# xl4432.net
KiCad netlist of a schematic drawn in EAGLE
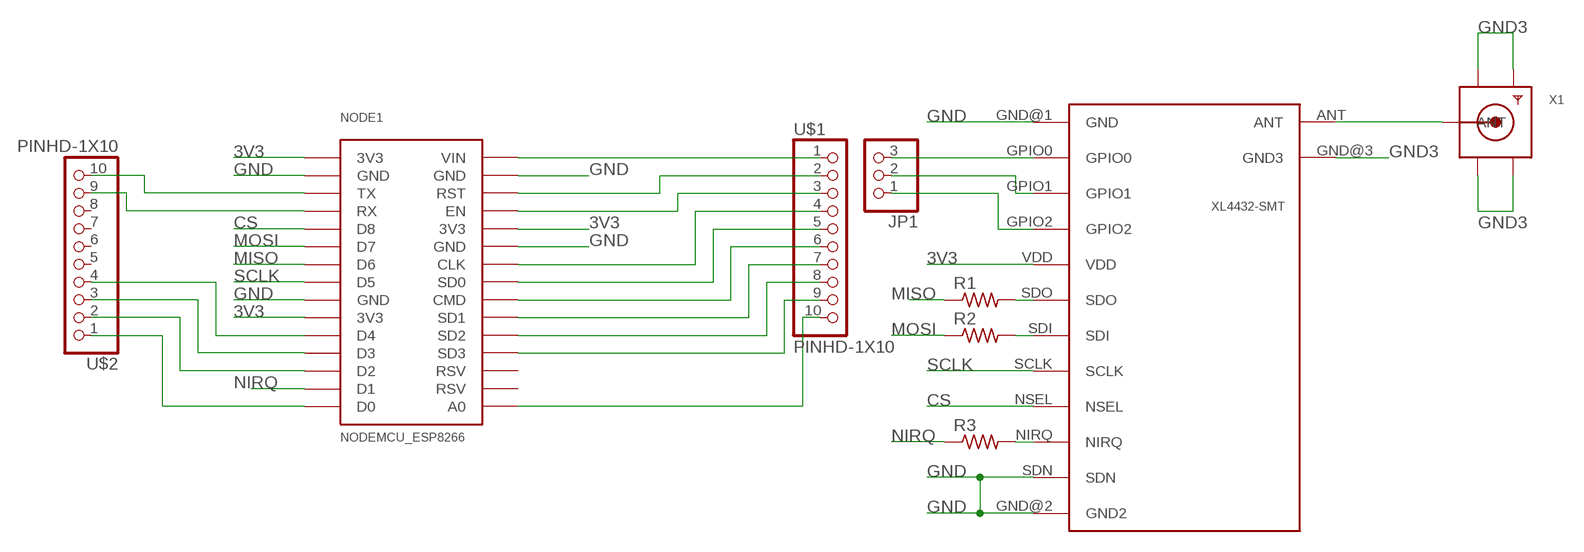
[diagram p0: schematic, sheet 1]

(export (version "E")
  (design (tool "Eeschema 10.0.6"))
  (components
    (comp (ref "4332-1")
      (value "XM4432-SMT")
      (footprint "eagle-import:XL4432-SMT")
      (libsource (lib "eagle-import") (part "XM4432-SMT"))
    )
    (comp (ref "JP1")
      (value "PINHD-1X3")
      (footprint "eagle-import:1X03")
      (libsource (lib "eagle-import") (part "PINHD-1X3"))
    )
    (comp (ref "NODE1")
      (value "NODEMCU_ESP8266")
      (footprint "eagle-import:NODEMCU_ESP8266")
      (libsource (lib "eagle-import") (part "NODEMCU_ESP8266"))
    )
    (comp (ref "R1")
      (value "R-US_R2012")
      (footprint "eagle-import:R2012")
      (libsource (lib "eagle-import") (part "R-US_R2012"))
    )
    (comp (ref "R2")
      (value "R-US_R2012")
      (footprint "eagle-import:R2012")
      (libsource (lib "eagle-import") (part "R-US_R2012"))
    )
    (comp (ref "R3")
      (value "R-US_R2012")
      (footprint "eagle-import:R2012")
      (libsource (lib "eagle-import") (part "R-US_R2012"))
    )
    (comp (ref "U$1")
      (value "PINHD-1X10")
      (footprint "eagle-import:1X10-BIG")
      (libsource (lib "eagle-import") (part "PINHD-1X10"))
    )
    (comp (ref "U$2")
      (value "PINHD-1X10")
      (footprint "eagle-import:1X10-BIG")
      (libsource (lib "eagle-import") (part "PINHD-1X10"))
    )
    (comp (ref "X1")
      (value "SMACONNECTOR")
      (footprint "eagle-import:SMA90_DIP")
      (libsource (lib "eagle-import") (part "SMACONNECTOR"))
    )
  )
  (nets
    (net (code "1") (name "/3V3") (class "Default")
      (node (ref "4332-1") (pin "VDD") (pinfunction "VDD_VDD") (pintype "power_in"))
      (node (ref "NODE1") (pin "3V3@1") (pinfunction "3V3_3V3@1") (pintype "power_in"))
      (node (ref "NODE1") (pin "3V3@2") (pinfunction "3V3_3V3@2") (pintype "power_in"))
      (node (ref "NODE1") (pin "3V3@3") (pinfunction "3V3_3V3@3") (pintype "power_in"))
    )
    (net (code "2") (name "/CS") (class "Default")
      (node (ref "4332-1") (pin "NSEL") (pinfunction "NSEL_NSEL") (pintype "bidirectional"))
      (node (ref "NODE1") (pin "D8") (pinfunction "D8_D8") (pintype "bidirectional"))
    )
    (net (code "3") (name "/GND") (class "Default")
      (node (ref "4332-1") (pin "GND@1") (pinfunction "GND_GND@1") (pintype "power_in"))
      (node (ref "4332-1") (pin "GND@2") (pinfunction "GND2_GND@2") (pintype "power_in"))
      (node (ref "4332-1") (pin "SDN") (pinfunction "SDN_SDN") (pintype "bidirectional"))
      (node (ref "NODE1") (pin "GND@1") (pinfunction "GND_GND@1") (pintype "power_in"))
      (node (ref "NODE1") (pin "GND@2") (pinfunction "GND_GND@2") (pintype "power_in"))
      (node (ref "NODE1") (pin "GND@3") (pinfunction "GND_GND@3") (pintype "power_in"))
      (node (ref "NODE1") (pin "GND@4") (pinfunction "GND_GND@4") (pintype "power_in"))
    )
    (net (code "4") (name "/GND3") (class "Default")
      (node (ref "4332-1") (pin "GND@3") (pinfunction "GND3_GND@3") (pintype "power_in"))
      (node (ref "X1") (pin "GND1") (pinfunction "GND1_GND1") (pintype "power_in"))
      (node (ref "X1") (pin "GND2") (pinfunction "GND2_GND2") (pintype "power_in"))
      (node (ref "X1") (pin "GND3") (pinfunction "GND3_GND3") (pintype "power_in"))
      (node (ref "X1") (pin "GND4") (pinfunction "GND4_GND4") (pintype "power_in"))
    )
    (net (code "5") (name "/MISO") (class "Default")
      (node (ref "NODE1") (pin "D6") (pinfunction "D6_D6") (pintype "bidirectional"))
      (node (ref "R1") (pin "1") (pinfunction "1_1") (pintype "passive"))
    )
    (net (code "6") (name "/MOSI") (class "Default")
      (node (ref "NODE1") (pin "D7") (pinfunction "D7_D7") (pintype "bidirectional"))
      (node (ref "R2") (pin "1") (pinfunction "1_1") (pintype "passive"))
    )
    (net (code "7") (name "/NIRQ") (class "Default")
      (node (ref "NODE1") (pin "D1") (pinfunction "D1_D1") (pintype "bidirectional"))
      (node (ref "R3") (pin "1") (pinfunction "1_1") (pintype "passive"))
    )
    (net (code "8") (name "/SCLK") (class "Default")
      (node (ref "4332-1") (pin "SCLK") (pinfunction "SCLK_SCLK") (pintype "bidirectional"))
      (node (ref "NODE1") (pin "D5") (pinfunction "D5_D5") (pintype "bidirectional"))
    )
    (net (code "9") (name "Net-(4332-1-PadGPIO0)") (class "Default")
      (node (ref "4332-1") (pin "GPIO0") (pinfunction "GPIO0_GPIO0") (pintype "bidirectional"))
      (node (ref "JP1") (pin "3") (pinfunction "3_3") (pintype "passive"))
    )
    (net (code "10") (name "Net-(4332-1-PadGPIO1)") (class "Default")
      (node (ref "4332-1") (pin "GPIO1") (pinfunction "GPIO1_GPIO1") (pintype "bidirectional"))
      (node (ref "JP1") (pin "2") (pinfunction "2_2") (pintype "passive"))
    )
    (net (code "11") (name "Net-(4332-1-PadGPIO2)") (class "Default")
      (node (ref "4332-1") (pin "GPIO2") (pinfunction "GPIO2_GPIO2") (pintype "bidirectional"))
      (node (ref "JP1") (pin "1") (pinfunction "1_1") (pintype "passive"))
    )
    (net (code "12") (name "Net-(4332-1-PadNIRQ)") (class "Default")
      (node (ref "4332-1") (pin "NIRQ") (pinfunction "NIRQ_NIRQ") (pintype "bidirectional"))
      (node (ref "R3") (pin "2") (pinfunction "2_2") (pintype "passive"))
    )
    (net (code "13") (name "Net-(4332-1-PadSDI)") (class "Default")
      (node (ref "4332-1") (pin "SDI") (pinfunction "SDI_SDI") (pintype "bidirectional"))
      (node (ref "R2") (pin "2") (pinfunction "2_2") (pintype "passive"))
    )
    (net (code "14") (name "Net-(4332-1-PadSDO)") (class "Default")
      (node (ref "4332-1") (pin "SDO") (pinfunction "SDO_SDO") (pintype "bidirectional"))
      (node (ref "R1") (pin "2") (pinfunction "2_2") (pintype "passive"))
    )
    (net (code "15") (name "Net-(NODE1-PadA0)") (class "Default")
      (node (ref "NODE1") (pin "A0") (pinfunction "A0_A0") (pintype "bidirectional"))
      (node (ref "U$1") (pin "10") (pinfunction "10_10") (pintype "passive"))
    )
    (net (code "16") (name "Net-(NODE1-PadCLK)") (class "Default")
      (node (ref "NODE1") (pin "CLK") (pinfunction "CLK_CLK") (pintype "bidirectional"))
      (node (ref "U$1") (pin "4") (pinfunction "4_4") (pintype "passive"))
    )
    (net (code "17") (name "Net-(NODE1-PadCMD)") (class "Default")
      (node (ref "NODE1") (pin "CMD") (pinfunction "CMD_CMD") (pintype "bidirectional"))
      (node (ref "U$1") (pin "6") (pinfunction "6_6") (pintype "passive"))
    )
    (net (code "18") (name "Net-(NODE1-PadD0)") (class "Default")
      (node (ref "NODE1") (pin "D0") (pinfunction "D0_D0") (pintype "bidirectional"))
      (node (ref "U$2") (pin "1") (pinfunction "1_1") (pintype "passive"))
    )
    (net (code "19") (name "Net-(NODE1-PadD2)") (class "Default")
      (node (ref "NODE1") (pin "D2") (pinfunction "D2_D2") (pintype "bidirectional"))
      (node (ref "U$2") (pin "2") (pinfunction "2_2") (pintype "passive"))
    )
    (net (code "20") (name "Net-(NODE1-PadD3)") (class "Default")
      (node (ref "NODE1") (pin "D3") (pinfunction "D3_D3") (pintype "bidirectional"))
      (node (ref "U$2") (pin "3") (pinfunction "3_3") (pintype "passive"))
    )
    (net (code "21") (name "Net-(NODE1-PadD4)") (class "Default")
      (node (ref "NODE1") (pin "D4") (pinfunction "D4_D4") (pintype "bidirectional"))
      (node (ref "U$2") (pin "4") (pinfunction "4_4") (pintype "passive"))
    )
    (net (code "22") (name "Net-(NODE1-PadEN)") (class "Default")
      (node (ref "NODE1") (pin "EN") (pinfunction "EN_EN") (pintype "bidirectional"))
      (node (ref "U$1") (pin "3") (pinfunction "3_3") (pintype "passive"))
    )
    (net (code "23") (name "Net-(NODE1-PadRST)") (class "Default")
      (node (ref "NODE1") (pin "RST") (pinfunction "RST_RST") (pintype "bidirectional"))
      (node (ref "U$1") (pin "2") (pinfunction "2_2") (pintype "passive"))
    )
    (net (code "24") (name "Net-(NODE1-PadRX)") (class "Default")
      (node (ref "NODE1") (pin "RX") (pinfunction "RX_RX") (pintype "bidirectional"))
      (node (ref "U$2") (pin "9") (pinfunction "9_9") (pintype "passive"))
    )
    (net (code "25") (name "Net-(NODE1-PadSD1)") (class "Default")
      (node (ref "NODE1") (pin "SD1") (pinfunction "SD1_SD1") (pintype "bidirectional"))
      (node (ref "U$1") (pin "7") (pinfunction "7_7") (pintype "passive"))
    )
    (net (code "26") (name "Net-(NODE1-PadSD2)") (class "Default")
      (node (ref "NODE1") (pin "SD2") (pinfunction "SD2_SD2") (pintype "bidirectional"))
      (node (ref "U$1") (pin "8") (pinfunction "8_8") (pintype "passive"))
    )
    (net (code "27") (name "Net-(NODE1-PadSD3)") (class "Default")
      (node (ref "NODE1") (pin "SD3") (pinfunction "SD3_SD3") (pintype "bidirectional"))
      (node (ref "U$1") (pin "9") (pinfunction "9_9") (pintype "passive"))
    )
    (net (code "28") (name "Net-(NODE1-PadTX)") (class "Default")
      (node (ref "NODE1") (pin "TX") (pinfunction "TX_TX") (pintype "bidirectional"))
      (node (ref "U$2") (pin "10") (pinfunction "10_10") (pintype "passive"))
    )
    (net (code "29") (name "Net-(NODE1-PadVIN)") (class "Default")
      (node (ref "NODE1") (pin "VIN") (pinfunction "VIN_VIN") (pintype "power_in"))
      (node (ref "U$1") (pin "1") (pinfunction "1_1") (pintype "passive"))
    )
    (net (code "30") (name "Net-(NODE1-SD0)") (class "Default")
      (node (ref "NODE1") (pin "SDO") (pinfunction "SD0_SDO") (pintype "bidirectional"))
      (node (ref "U$1") (pin "5") (pinfunction "5_5") (pintype "passive"))
    )
    (net (code "31") (name "Net-(X1-ANT)") (class "Default")
      (node (ref "4332-1") (pin "ANT") (pinfunction "ANT_ANT") (pintype "input"))
      (node (ref "X1") (pin "ANTENNA") (pinfunction "ANT_ANTENNA") (pintype "bidirectional"))
    )
    (net (code "32") (name "unconnected-(NODE1-RSV-PadRSV1)") (class "Default")
      (node (ref "NODE1") (pin "RSV1") (pinfunction "RSV_RSV1") (pintype "bidirectional"))
    )
    (net (code "33") (name "unconnected-(NODE1-RSV-PadRSV2)") (class "Default")
      (node (ref "NODE1") (pin "RSV2") (pinfunction "RSV_RSV2") (pintype "bidirectional"))
    )
    (net (code "34") (name "unconnected-(U$2-Pad5)") (class "Default")
      (node (ref "U$2") (pin "5") (pinfunction "5_5") (pintype "passive"))
    )
    (net (code "35") (name "unconnected-(U$2-Pad6)") (class "Default")
      (node (ref "U$2") (pin "6") (pinfunction "6_6") (pintype "passive"))
    )
    (net (code "36") (name "unconnected-(U$2-Pad7)") (class "Default")
      (node (ref "U$2") (pin "7") (pinfunction "7_7") (pintype "passive"))
    )
    (net (code "37") (name "unconnected-(U$2-Pad8)") (class "Default")
      (node (ref "U$2") (pin "8") (pinfunction "8_8") (pintype "passive"))
    )
  )
)
